# raspi.net
KiCad netlist of a schematic drawn in Altium Designer
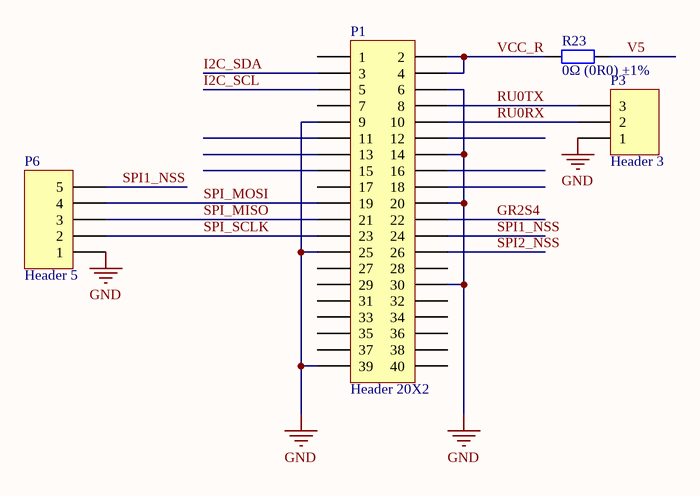
[diagram p0: raspi.SchDoc]

(export (version "E")
  (design (tool "Eeschema 10.0.6"))
  (components
    (comp (ref "P1")
      (value "Header 20X2")
      (footprint "HDR2X20")
      (description "Header, 20-Pin, Dual row")
      (fields (field (name "PUBLISHER") "Altium Limited"))
      (libsource (lib "Miscellaneous Connectors") (part "Header 20X2"))
    )
    (comp (ref "P3")
      (value "Header 3")
      (footprint "HDR1X3")
      (description "Header, 3-Pin")
      (fields (field (name "PUBLISHER") "Altium Limited"))
      (libsource (lib "Miscellaneous Connectors") (part "Header 3"))
    )
    (comp (ref "P6")
      (value "Header 5")
      (footprint "HDR1X5")
      (description "Header, 5-Pin")
      (fields (field (name "PUBLISHER") "Altium Limited"))
      (libsource (lib "Miscellaneous Connectors") (part "Header 5"))
    )
    (comp (ref "R23")
      (value "0Ω (0R0) ±1%")
      (footprint "1206_R")
      (description "贴片电阻")
      (libsource (lib "Miscellaneous Devices LC") (part "1206 0Ω (0R0) 1%"))
    )
  )
  (nets
    (net (code "1") (name "/GR2S4") (class "Default")
      (node (ref "P1") (pin "22") (pinfunction "22_22") (pintype "passive"))
    )
    (net (code "2") (name "/I2C_SCL") (class "Default")
      (node (ref "P1") (pin "5") (pinfunction "5_5") (pintype "passive"))
    )
    (net (code "3") (name "/I2C_SDA") (class "Default")
      (node (ref "P1") (pin "3") (pinfunction "3_3") (pintype "passive"))
    )
    (net (code "4") (name "/RU0RX") (class "Default")
      (node (ref "P1") (pin "10") (pinfunction "10_10") (pintype "passive"))
      (node (ref "P3") (pin "2") (pinfunction "2_2") (pintype "passive"))
    )
    (net (code "5") (name "/RU0TX") (class "Default")
      (node (ref "P1") (pin "8") (pinfunction "8_8") (pintype "passive"))
      (node (ref "P3") (pin "3") (pinfunction "3_3") (pintype "passive"))
    )
    (net (code "6") (name "/SPI1_NSS") (class "Default")
      (node (ref "P1") (pin "24") (pinfunction "24_24") (pintype "passive"))
      (node (ref "P6") (pin "5") (pinfunction "5_5") (pintype "passive"))
    )
    (net (code "7") (name "/SPI2_NSS") (class "Default")
      (node (ref "P1") (pin "26") (pinfunction "26_26") (pintype "passive"))
    )
    (net (code "8") (name "/SPI_MISO") (class "Default")
      (node (ref "P1") (pin "21") (pinfunction "21_21") (pintype "passive"))
      (node (ref "P6") (pin "3") (pinfunction "3_3") (pintype "passive"))
    )
    (net (code "9") (name "/SPI_MOSI") (class "Default")
      (node (ref "P1") (pin "19") (pinfunction "19_19") (pintype "passive"))
      (node (ref "P6") (pin "4") (pinfunction "4_4") (pintype "passive"))
    )
    (net (code "10") (name "/SPI_SCLK") (class "Default")
      (node (ref "P1") (pin "23") (pinfunction "23_23") (pintype "passive"))
      (node (ref "P6") (pin "2") (pinfunction "2_2") (pintype "passive"))
    )
    (net (code "11") (name "/V5") (class "Default")
      (node (ref "R23") (pin "2") (pinfunction "2_2") (pintype "passive"))
    )
    (net (code "12") (name "/VCC_R") (class "Default")
      (node (ref "P1") (pin "2") (pinfunction "2_2") (pintype "passive"))
      (node (ref "P1") (pin "4") (pinfunction "4_4") (pintype "passive"))
      (node (ref "R23") (pin "1") (pinfunction "1_1") (pintype "passive"))
    )
    (net (code "13") (name "GND") (class "Default")
      (node (ref "P1") (pin "14") (pinfunction "14_14") (pintype "passive"))
      (node (ref "P1") (pin "20") (pinfunction "20_20") (pintype "passive"))
      (node (ref "P1") (pin "25") (pinfunction "25_25") (pintype "passive"))
      (node (ref "P1") (pin "30") (pinfunction "30_30") (pintype "passive"))
      (node (ref "P1") (pin "39") (pinfunction "39_39") (pintype "passive"))
      (node (ref "P1") (pin "6") (pinfunction "6_6") (pintype "passive"))
      (node (ref "P1") (pin "9") (pinfunction "9_9") (pintype "passive"))
      (node (ref "P3") (pin "1") (pinfunction "1_1") (pintype "passive"))
      (node (ref "P6") (pin "1") (pinfunction "1_1") (pintype "passive"))
    )
    (net (code "14") (name "unconnected-(P1-Pad1)") (class "Default")
      (node (ref "P1") (pin "1") (pinfunction "1_1") (pintype "passive"))
    )
    (net (code "15") (name "unconnected-(P1-Pad7)") (class "Default")
      (node (ref "P1") (pin "7") (pinfunction "7_7") (pintype "passive"))
    )
    (net (code "16") (name "unconnected-(P1-Pad11)") (class "Default")
      (node (ref "P1") (pin "11") (pinfunction "11_11") (pintype "passive"))
    )
    (net (code "17") (name "unconnected-(P1-Pad12)") (class "Default")
      (node (ref "P1") (pin "12") (pinfunction "12_12") (pintype "passive"))
    )
    (net (code "18") (name "unconnected-(P1-Pad13)") (class "Default")
      (node (ref "P1") (pin "13") (pinfunction "13_13") (pintype "passive"))
    )
    (net (code "19") (name "unconnected-(P1-Pad15)") (class "Default")
      (node (ref "P1") (pin "15") (pinfunction "15_15") (pintype "passive"))
    )
    (net (code "20") (name "unconnected-(P1-Pad16)") (class "Default")
      (node (ref "P1") (pin "16") (pinfunction "16_16") (pintype "passive"))
    )
    (net (code "21") (name "unconnected-(P1-Pad17)") (class "Default")
      (node (ref "P1") (pin "17") (pinfunction "17_17") (pintype "passive"))
    )
    (net (code "22") (name "unconnected-(P1-Pad18)") (class "Default")
      (node (ref "P1") (pin "18") (pinfunction "18_18") (pintype "passive"))
    )
    (net (code "23") (name "unconnected-(P1-Pad27)") (class "Default")
      (node (ref "P1") (pin "27") (pinfunction "27_27") (pintype "passive"))
    )
    (net (code "24") (name "unconnected-(P1-Pad28)") (class "Default")
      (node (ref "P1") (pin "28") (pinfunction "28_28") (pintype "passive"))
    )
    (net (code "25") (name "unconnected-(P1-Pad29)") (class "Default")
      (node (ref "P1") (pin "29") (pinfunction "29_29") (pintype "passive"))
    )
    (net (code "26") (name "unconnected-(P1-Pad31)") (class "Default")
      (node (ref "P1") (pin "31") (pinfunction "31_31") (pintype "passive"))
    )
    (net (code "27") (name "unconnected-(P1-Pad32)") (class "Default")
      (node (ref "P1") (pin "32") (pinfunction "32_32") (pintype "passive"))
    )
    (net (code "28") (name "unconnected-(P1-Pad33)") (class "Default")
      (node (ref "P1") (pin "33") (pinfunction "33_33") (pintype "passive"))
    )
    (net (code "29") (name "unconnected-(P1-Pad34)") (class "Default")
      (node (ref "P1") (pin "34") (pinfunction "34_34") (pintype "passive"))
    )
    (net (code "30") (name "unconnected-(P1-Pad35)") (class "Default")
      (node (ref "P1") (pin "35") (pinfunction "35_35") (pintype "passive"))
    )
    (net (code "31") (name "unconnected-(P1-Pad36)") (class "Default")
      (node (ref "P1") (pin "36") (pinfunction "36_36") (pintype "passive"))
    )
    (net (code "32") (name "unconnected-(P1-Pad37)") (class "Default")
      (node (ref "P1") (pin "37") (pinfunction "37_37") (pintype "passive"))
    )
    (net (code "33") (name "unconnected-(P1-Pad38)") (class "Default")
      (node (ref "P1") (pin "38") (pinfunction "38_38") (pintype "passive"))
    )
    (net (code "34") (name "unconnected-(P1-Pad40)") (class "Default")
      (node (ref "P1") (pin "40") (pinfunction "40_40") (pintype "passive"))
    )
  )
)
